# 1-Schematic_Xmas-tree_EASYEDA.net
KiCad netlist of a schematic drawn in EasyEDA
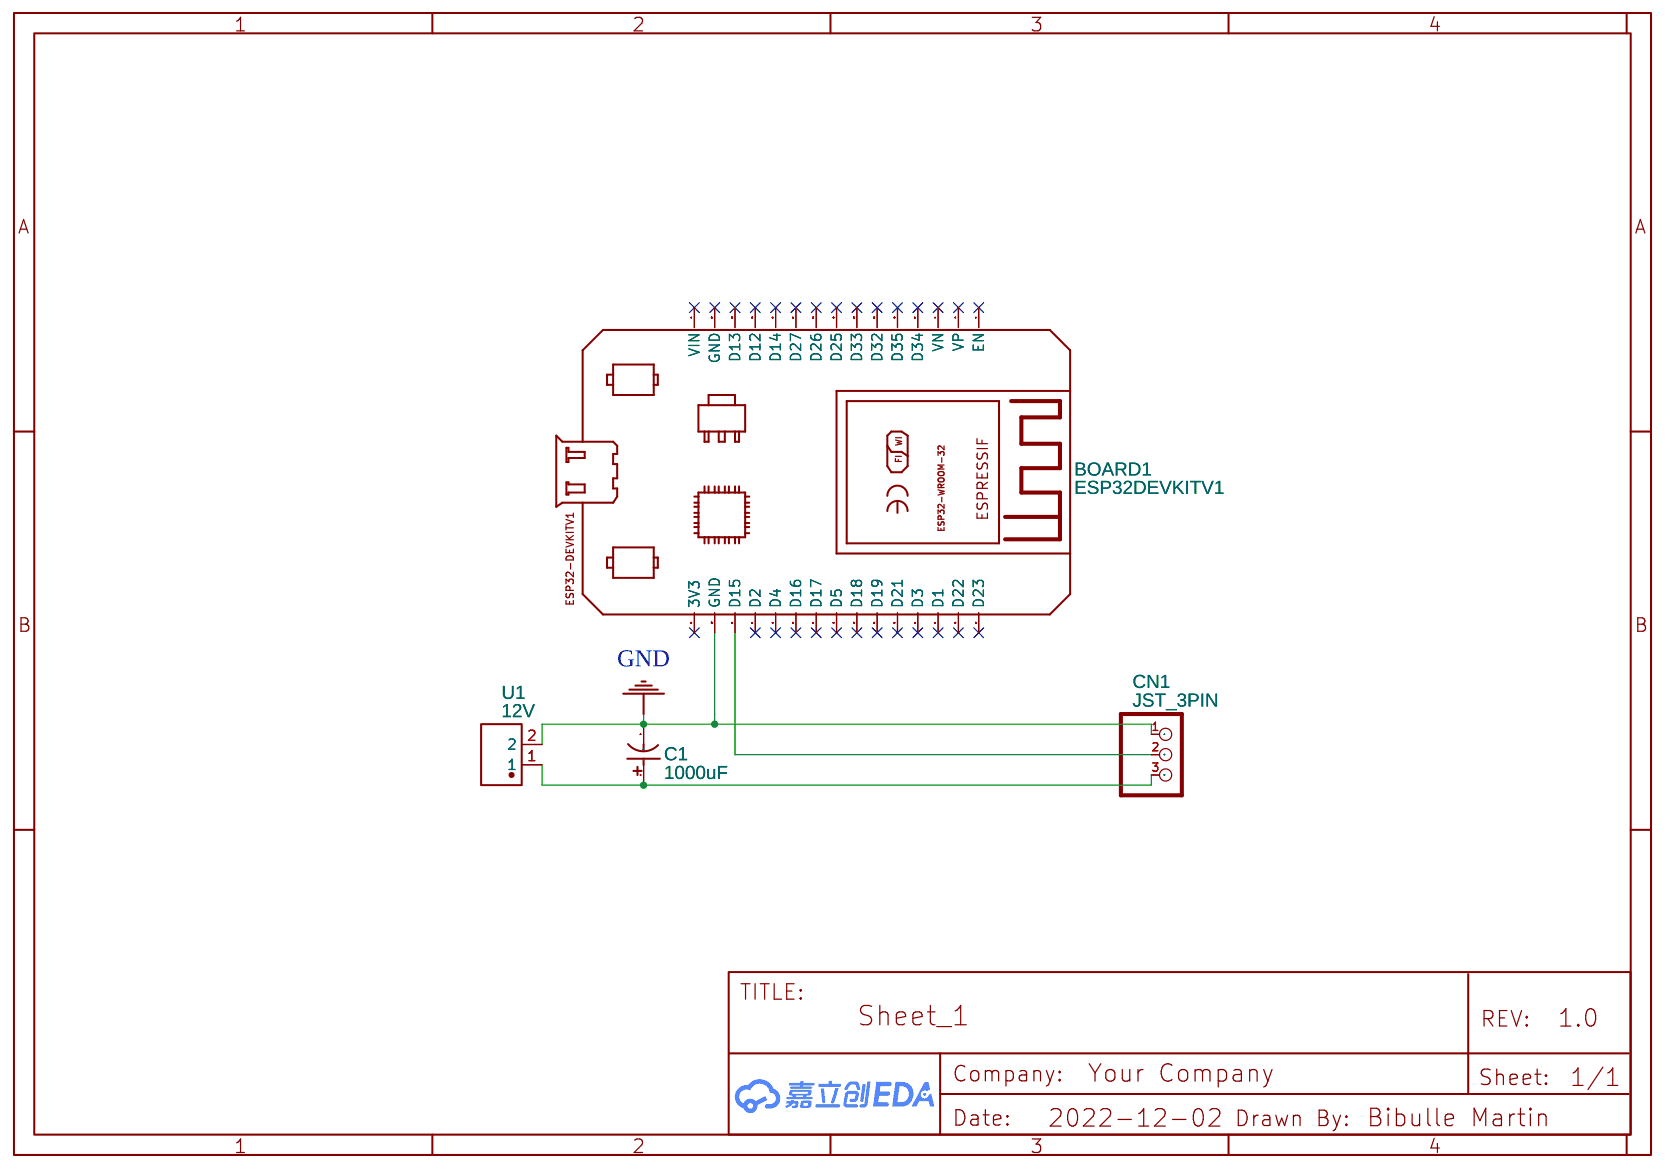
[diagram p0: schematic sheet]

(export (version "E")
  (design (tool "Eeschema 10.0.6"))
  (components
    (comp (ref "BOARD1") (value "ESP32DEVKITV1") (libsource (lib "") (part "ESP32DEVKITV1")))
    (comp (ref "C1")
      (value "1000uF")
      (fields (field (name "Manufacturer Part") "1000uF 16V 8*16") (field (name "Manufacturer") "ValuePro"))
      (libsource (lib "") (part "1000uF 16V 8*16"))
    )
    (comp (ref "CN1") (value "JST_3PIN") (libsource (lib "") (part "JST_3PIN")))
    (comp (ref "U1")
      (value "12V")
      (fields
        (field (name "Manufacturer Part") "DB127V-5.0-2P-GN-S")
        (field (name "Manufacturer") "DIBO(地博电气)")
      )
      (libsource (lib "") (part "DB127V-5.0-2P"))
    )
  )
  (nets
    (net (code "1") (name "GND") (class "Default")
      (node (ref "BOARD1") (pin "GND@1") (pinfunction "GND_GND@1") (pintype "bidirectional"))
      (node (ref "C1") (pin "2") (pinfunction "2_2") (pintype "input"))
      (node (ref "CN1") (pin "1") (pinfunction "1_1") (pintype "unspecified"))
      (node (ref "U1") (pin "2") (pinfunction "2_2") (pintype "unspecified"))
    )
    (net (code "2") (name "Net-(BOARD1-PadD15)") (class "Default")
      (node (ref "BOARD1") (pin "D15") (pinfunction "D15_D15") (pintype "bidirectional"))
      (node (ref "CN1") (pin "2") (pinfunction "2_2") (pintype "unspecified"))
    )
    (net (code "3") (name "Net-(C1-Pad1)") (class "Default")
      (node (ref "C1") (pin "1") (pinfunction "1_1") (pintype "input"))
      (node (ref "CN1") (pin "3") (pinfunction "3_3") (pintype "unspecified"))
      (node (ref "U1") (pin "1") (pinfunction "1_1") (pintype "unspecified"))
    )
    (net (code "4") (name "unconnected-(BOARD1-Pad3V3)") (class "Default")
      (node (ref "BOARD1") (pin "3V3") (pinfunction "3V3_3V3") (pintype "bidirectional+no_connect"))
    )
    (net (code "5") (name "unconnected-(BOARD1-PadD1)") (class "Default")
      (node (ref "BOARD1") (pin "D1") (pinfunction "D1_D1") (pintype "bidirectional+no_connect"))
    )
    (net (code "6") (name "unconnected-(BOARD1-PadD2)") (class "Default")
      (node (ref "BOARD1") (pin "D2") (pinfunction "D2_D2") (pintype "bidirectional+no_connect"))
    )
    (net (code "7") (name "unconnected-(BOARD1-PadD3)") (class "Default")
      (node (ref "BOARD1") (pin "D3") (pinfunction "D3_D3") (pintype "bidirectional+no_connect"))
    )
    (net (code "8") (name "unconnected-(BOARD1-PadD4)") (class "Default")
      (node (ref "BOARD1") (pin "D4") (pinfunction "D4_D4") (pintype "bidirectional+no_connect"))
    )
    (net (code "9") (name "unconnected-(BOARD1-PadD5)") (class "Default")
      (node (ref "BOARD1") (pin "D5") (pinfunction "D5_D5") (pintype "bidirectional+no_connect"))
    )
    (net (code "10") (name "unconnected-(BOARD1-PadD12)") (class "Default")
      (node (ref "BOARD1") (pin "D12") (pinfunction "D12_D12") (pintype "bidirectional+no_connect"))
    )
    (net (code "11") (name "unconnected-(BOARD1-PadD13)") (class "Default")
      (node (ref "BOARD1") (pin "D13") (pinfunction "D13_D13") (pintype "bidirectional+no_connect"))
    )
    (net (code "12") (name "unconnected-(BOARD1-PadD14)") (class "Default")
      (node (ref "BOARD1") (pin "D14") (pinfunction "D14_D14") (pintype "bidirectional+no_connect"))
    )
    (net (code "13") (name "unconnected-(BOARD1-PadD16)") (class "Default")
      (node (ref "BOARD1") (pin "D16") (pinfunction "D16_D16") (pintype "bidirectional+no_connect"))
    )
    (net (code "14") (name "unconnected-(BOARD1-PadD17)") (class "Default")
      (node (ref "BOARD1") (pin "D17") (pinfunction "D17_D17") (pintype "bidirectional+no_connect"))
    )
    (net (code "15") (name "unconnected-(BOARD1-PadD18)") (class "Default")
      (node (ref "BOARD1") (pin "D18") (pinfunction "D18_D18") (pintype "bidirectional+no_connect"))
    )
    (net (code "16") (name "unconnected-(BOARD1-PadD19)") (class "Default")
      (node (ref "BOARD1") (pin "D19") (pinfunction "D19_D19") (pintype "bidirectional+no_connect"))
    )
    (net (code "17") (name "unconnected-(BOARD1-PadD21)") (class "Default")
      (node (ref "BOARD1") (pin "D21") (pinfunction "D21_D21") (pintype "bidirectional+no_connect"))
    )
    (net (code "18") (name "unconnected-(BOARD1-PadD22)") (class "Default")
      (node (ref "BOARD1") (pin "D22") (pinfunction "D22_D22") (pintype "bidirectional+no_connect"))
    )
    (net (code "19") (name "unconnected-(BOARD1-PadD23)") (class "Default")
      (node (ref "BOARD1") (pin "D23") (pinfunction "D23_D23") (pintype "bidirectional+no_connect"))
    )
    (net (code "20") (name "unconnected-(BOARD1-PadD25)") (class "Default")
      (node (ref "BOARD1") (pin "D25") (pinfunction "D25_D25") (pintype "bidirectional+no_connect"))
    )
    (net (code "21") (name "unconnected-(BOARD1-PadD26)") (class "Default")
      (node (ref "BOARD1") (pin "D26") (pinfunction "D26_D26") (pintype "bidirectional+no_connect"))
    )
    (net (code "22") (name "unconnected-(BOARD1-PadD27)") (class "Default")
      (node (ref "BOARD1") (pin "D27") (pinfunction "D27_D27") (pintype "bidirectional+no_connect"))
    )
    (net (code "23") (name "unconnected-(BOARD1-PadD32)") (class "Default")
      (node (ref "BOARD1") (pin "D32") (pinfunction "D32_D32") (pintype "bidirectional+no_connect"))
    )
    (net (code "24") (name "unconnected-(BOARD1-PadD33)") (class "Default")
      (node (ref "BOARD1") (pin "D33") (pinfunction "D33_D33") (pintype "bidirectional+no_connect"))
    )
    (net (code "25") (name "unconnected-(BOARD1-PadD34)") (class "Default")
      (node (ref "BOARD1") (pin "D34") (pinfunction "D34_D34") (pintype "bidirectional+no_connect"))
    )
    (net (code "26") (name "unconnected-(BOARD1-PadD35)") (class "Default")
      (node (ref "BOARD1") (pin "D35") (pinfunction "D35_D35") (pintype "bidirectional+no_connect"))
    )
    (net (code "27") (name "unconnected-(BOARD1-PadEN)") (class "Default")
      (node (ref "BOARD1") (pin "EN") (pinfunction "EN_EN") (pintype "bidirectional+no_connect"))
    )
    (net (code "28") (name "unconnected-(BOARD1-PadGND)") (class "Default")
      (node (ref "BOARD1") (pin "GND") (pinfunction "GND_GND") (pintype "bidirectional+no_connect"))
    )
    (net (code "29") (name "unconnected-(BOARD1-PadVIN)") (class "Default")
      (node (ref "BOARD1") (pin "VIN") (pinfunction "VIN_VIN") (pintype "bidirectional+no_connect"))
    )
    (net (code "30") (name "unconnected-(BOARD1-PadVN)") (class "Default")
      (node (ref "BOARD1") (pin "VN") (pinfunction "VN_VN") (pintype "bidirectional+no_connect"))
    )
    (net (code "31") (name "unconnected-(BOARD1-PadVP)") (class "Default")
      (node (ref "BOARD1") (pin "VP") (pinfunction "VP_VP") (pintype "bidirectional+no_connect"))
    )
  )
)
